# Wattuino-Nanite841_v11.net
KiCad netlist of a schematic drawn in EAGLE
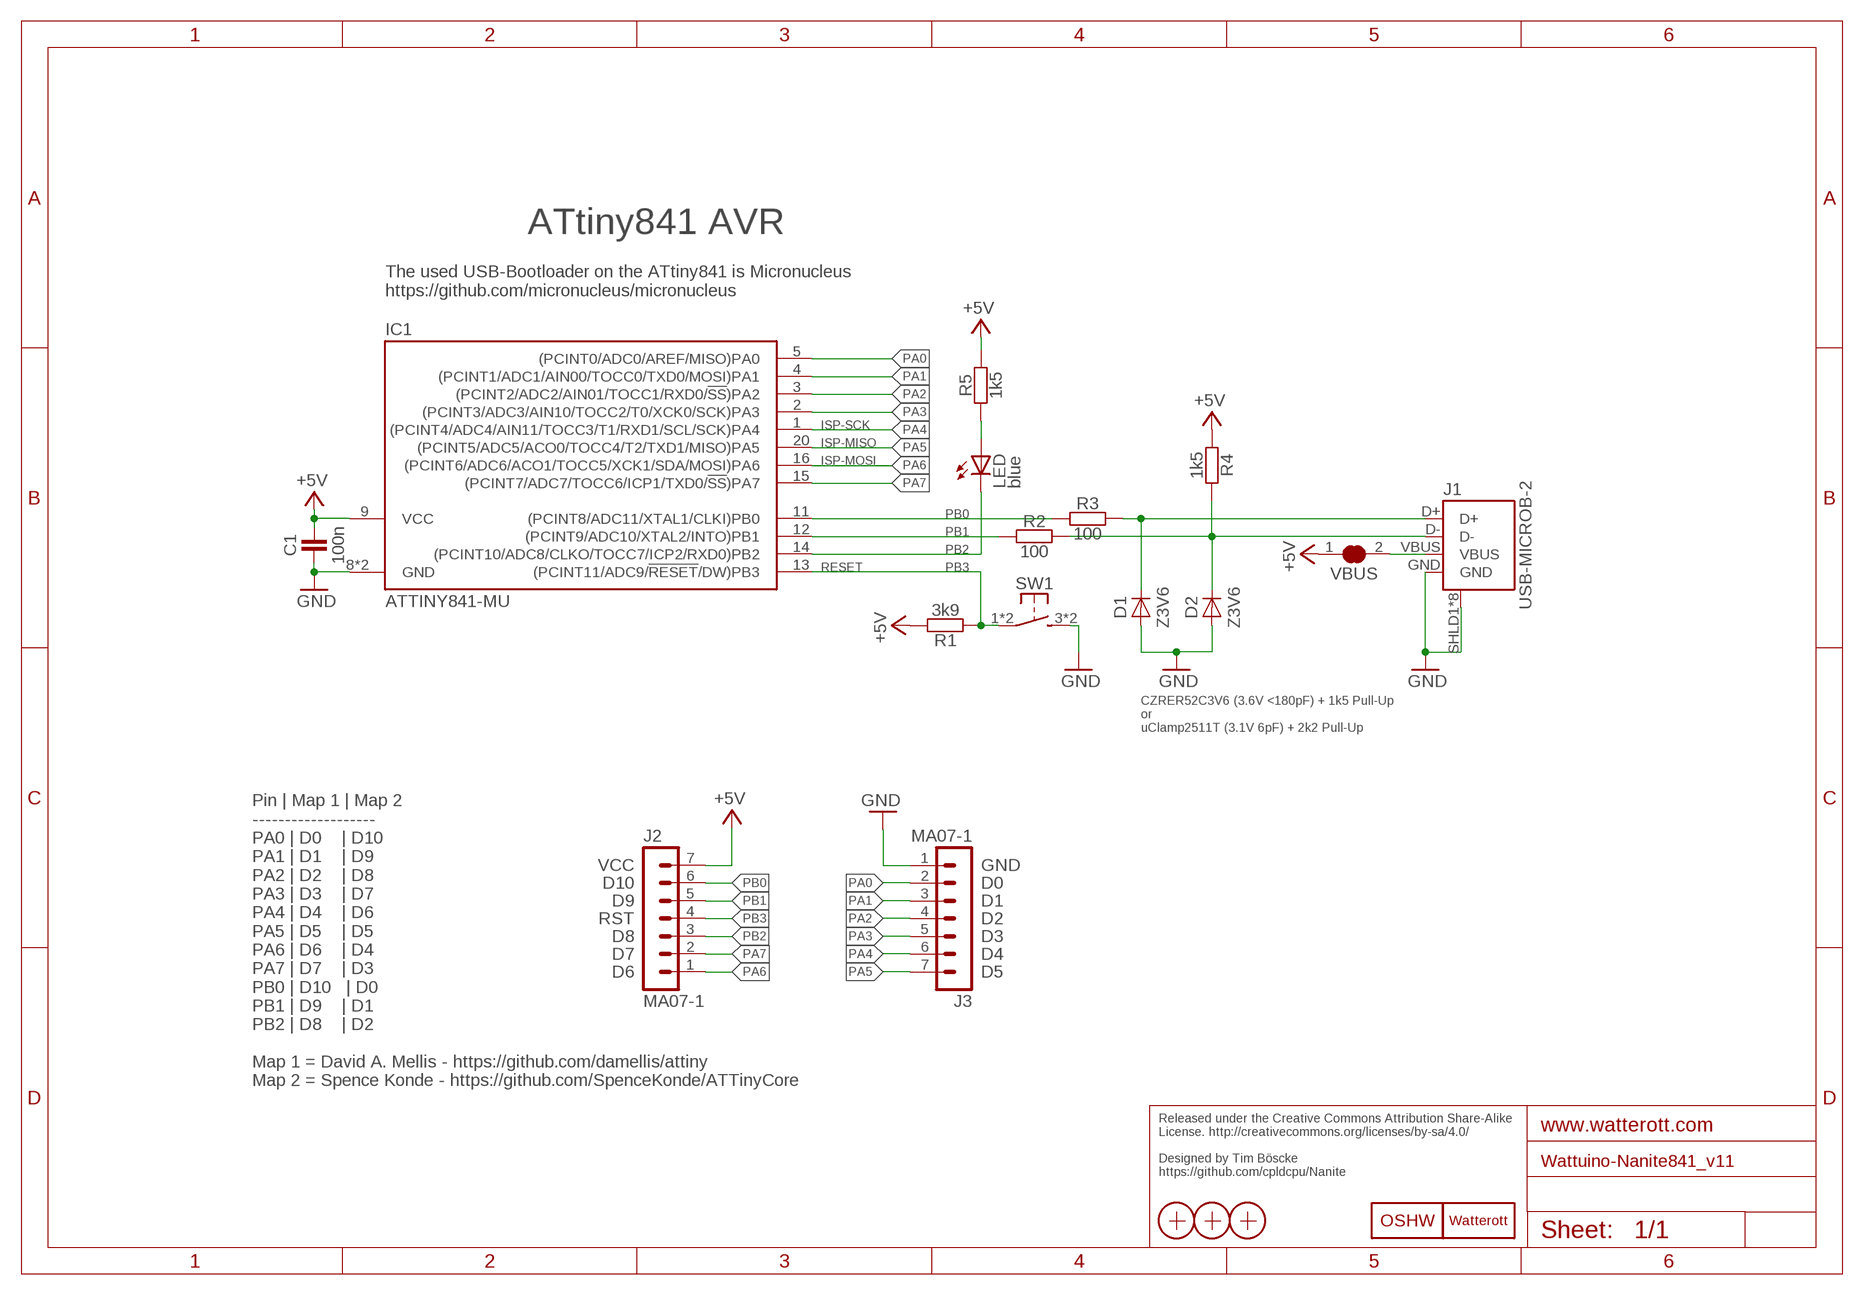
[diagram p0: schematic, sheet 1]

(export (version "E")
  (design (tool "Eeschema 10.0.6"))
  (components
    (comp (ref "C1")
      (value "100n")
      (footprint "eagle-import:C0402")
      (libsource (lib "eagle-import") (part "CAPACITOR-0402"))
    )
    (comp (ref "D1")
      (value "Z3V6")
      (footprint "eagle-import:SOD882")
      (libsource (lib "eagle-import") (part "DIODE-SOD882"))
    )
    (comp (ref "D2")
      (value "Z3V6")
      (footprint "eagle-import:SOD882")
      (libsource (lib "eagle-import") (part "DIODE-SOD882"))
    )
    (comp (ref "IC1")
      (value "ATTINY841-MU")
      (footprint "eagle-import:QFN20-PAD")
      (libsource (lib "eagle-import") (part "ATTINY841-MU"))
    )
    (comp (ref "J1")
      (value "USB-MICROB-2")
      (footprint "eagle-import:USB-MICROB-10118194")
      (libsource (lib "eagle-import") (part "USB-MICROB-2"))
    )
    (comp (ref "J2")
      (value "MA07-1")
      (footprint "eagle-import:MA07-1")
      (libsource (lib "eagle-import") (part "MA07-1"))
    )
    (comp (ref "J3")
      (value "MA07-1")
      (footprint "eagle-import:MA07-1")
      (libsource (lib "eagle-import") (part "MA07-1"))
    )
    (comp (ref "LED")
      (value "blue")
      (footprint "eagle-import:C0603")
      (libsource (lib "eagle-import") (part "LED-0603"))
    )
    (comp (ref "LOGO1")
      (value "LOGO-S_PLACE_S")
      (footprint "eagle-import:SPARK_TPLACE_S")
      (libsource (lib "eagle-import") (part "LOGO-S_PLACE_S"))
    )
    (comp (ref "LOGO2")
      (value "OSHW_LOGOX0070")
      (footprint "eagle-import:OSHW_6X70")
      (libsource (lib "eagle-import") (part "OSHW_LOGOX0070"))
    )
    (comp (ref "R1")
      (value "3k9")
      (footprint "eagle-import:C0402")
      (libsource (lib "eagle-import") (part "RESISTOR-0402"))
    )
    (comp (ref "R2")
      (value "100")
      (footprint "eagle-import:C0402")
      (libsource (lib "eagle-import") (part "RESISTOR-0402"))
    )
    (comp (ref "R3")
      (value "100")
      (footprint "eagle-import:C0402")
      (libsource (lib "eagle-import") (part "RESISTOR-0402"))
    )
    (comp (ref "R4")
      (value "1k5")
      (footprint "eagle-import:C0402")
      (libsource (lib "eagle-import") (part "RESISTOR-0402"))
    )
    (comp (ref "R5")
      (value "1k5")
      (footprint "eagle-import:C0402")
      (libsource (lib "eagle-import") (part "RESISTOR-0402"))
    )
    (comp (ref "SW1")
      (value "SW-TACTILE-PTS840P")
      (footprint "eagle-import:PTS840P")
      (libsource (lib "eagle-import") (part "SW-TACTILE-PTS840P"))
    )
    (comp (ref "VBUS")
      (value "JUMPER2-0603-NC")
      (footprint "eagle-import:JUMPER2-0603_NC")
      (libsource (lib "eagle-import") (part "JUMPER2-0603-NC"))
    )
    (comp (ref "X1")
      (value "PASSER-07")
      (footprint "eagle-import:PASSER_07MM")
      (libsource (lib "eagle-import") (part "PASSER-07"))
    )
    (comp (ref "X2")
      (value "PASSER-07")
      (footprint "eagle-import:PASSER_07MM")
      (libsource (lib "eagle-import") (part "PASSER-07"))
    )
    (comp (ref "X3")
      (value "PASSER-07")
      (footprint "eagle-import:PASSER_07MM")
      (libsource (lib "eagle-import") (part "PASSER-07"))
    )
  )
  (nets
    (net (code "1") (name "+5V") (class "Default")
      (node (ref "C1") (pin "2") (pinfunction "2_2") (pintype "passive"))
      (node (ref "IC1") (pin "9") (pinfunction "VCC_9") (pintype "power_in"))
      (node (ref "J2") (pin "7") (pinfunction "7_7") (pintype "passive"))
      (node (ref "R1") (pin "2") (pinfunction "2_2") (pintype "passive"))
      (node (ref "R4") (pin "1") (pinfunction "1_1") (pintype "passive"))
      (node (ref "R5") (pin "2") (pinfunction "2_2") (pintype "passive"))
      (node (ref "VBUS") (pin "1") (pinfunction "1_1") (pintype "passive"))
    )
    (net (code "2") (name "GND") (class "Default")
      (node (ref "C1") (pin "1") (pinfunction "1_1") (pintype "passive"))
      (node (ref "D1") (pin "A") (pinfunction "A_A") (pintype "passive"))
      (node (ref "D2") (pin "A") (pinfunction "A_A") (pintype "passive"))
      (node (ref "IC1") (pin "8") (pinfunction "GND_8") (pintype "power_in"))
      (node (ref "IC1") (pin "TP") (pinfunction "GND_TP") (pintype "power_in"))
      (node (ref "J1") (pin "GND") (pinfunction "GND_GND") (pintype "power_in"))
      (node (ref "J1") (pin "SHLD1") (pinfunction "SHIELD_SHLD1") (pintype "passive"))
      (node (ref "J1") (pin "SHLD2") (pinfunction "SHIELD_SHLD2") (pintype "passive"))
      (node (ref "J1") (pin "SHLD3") (pinfunction "SHIELD_SHLD3") (pintype "passive"))
      (node (ref "J1") (pin "SHLD4") (pinfunction "SHIELD_SHLD4") (pintype "passive"))
      (node (ref "J1") (pin "SHLD5") (pinfunction "SHIELD_SHLD5") (pintype "passive"))
      (node (ref "J1") (pin "SHLD6") (pinfunction "SHIELD_SHLD6") (pintype "passive"))
      (node (ref "J1") (pin "SHLD7") (pinfunction "SHIELD_SHLD7") (pintype "passive"))
      (node (ref "J1") (pin "SHLD8") (pinfunction "SHIELD_SHLD8") (pintype "passive"))
      (node (ref "J3") (pin "1") (pinfunction "1_1") (pintype "passive"))
      (node (ref "SW1") (pin "3") (pinfunction "S1_3") (pintype "passive"))
      (node (ref "SW1") (pin "4") (pinfunction "S1_4") (pintype "passive"))
    )
    (net (code "3") (name "Net-(D1-PadC)") (class "Default")
      (node (ref "D1") (pin "C") (pinfunction "C_C") (pintype "passive"))
      (node (ref "J1") (pin "D+") (pinfunction "D+_D+") (pintype "bidirectional"))
      (node (ref "R3") (pin "2") (pinfunction "2_2") (pintype "passive"))
    )
    (net (code "4") (name "Net-(D2-PadC)") (class "Default")
      (node (ref "D2") (pin "C") (pinfunction "C_C") (pintype "passive"))
      (node (ref "J1") (pin "D-") (pinfunction "D-_D-") (pintype "bidirectional"))
      (node (ref "R2") (pin "2") (pinfunction "2_2") (pintype "passive"))
      (node (ref "R4") (pin "2") (pinfunction "2_2") (pintype "passive"))
    )
    (net (code "5") (name "Net-(J1-PadVBUS)") (class "Default")
      (node (ref "J1") (pin "VBUS") (pinfunction "VBUS_VBUS") (pintype "power_in"))
      (node (ref "VBUS") (pin "2") (pinfunction "2_2") (pintype "passive"))
    )
    (net (code "6") (name "Net-(LED-PadA)") (class "Default")
      (node (ref "LED") (pin "A") (pinfunction "A_A") (pintype "passive"))
      (node (ref "R5") (pin "1") (pinfunction "1_1") (pintype "passive"))
    )
    (net (code "7") (name "PA0") (class "Default")
      (node (ref "IC1") (pin "5") (pinfunction "(PCINT0/ADC0/AREF/MISO)PA0_5") (pintype "bidirectional"))
      (node (ref "J3") (pin "2") (pinfunction "2_2") (pintype "passive"))
    )
    (net (code "8") (name "PA1") (class "Default")
      (node (ref "IC1") (pin "4") (pinfunction "(PCINT1/ADC1/AIN00/TOCC0/TXD0/MOSI)PA1_4") (pintype "bidirectional"))
      (node (ref "J3") (pin "3") (pinfunction "3_3") (pintype "passive"))
    )
    (net (code "9") (name "PA2") (class "Default")
      (node (ref "IC1") (pin "3") (pinfunction "(PCINT2/ADC2/AIN01/TOCC1/RXD0/~{SS})PA2_3") (pintype "bidirectional"))
      (node (ref "J3") (pin "4") (pinfunction "4_4") (pintype "passive"))
    )
    (net (code "10") (name "PA3") (class "Default")
      (node (ref "IC1") (pin "2") (pinfunction "(PCINT3/ADC3/AIN10/TOCC2/T0/XCK0/SCK)PA3_2") (pintype "bidirectional"))
      (node (ref "J3") (pin "5") (pinfunction "5_5") (pintype "passive"))
    )
    (net (code "11") (name "PA4") (class "Default")
      (node (ref "IC1") (pin "1") (pinfunction "(PCINT4/ADC4/AIN11/TOCC3/T1/RXD1/SCL/SCK)PA4_1") (pintype "bidirectional"))
      (node (ref "J3") (pin "6") (pinfunction "6_6") (pintype "passive"))
    )
    (net (code "12") (name "PA5") (class "Default")
      (node (ref "IC1") (pin "20") (pinfunction "(PCINT5/ADC5/ACO0/TOCC4/T2/TXD1/MISO)PA5_20") (pintype "bidirectional"))
      (node (ref "J3") (pin "7") (pinfunction "7_7") (pintype "passive"))
    )
    (net (code "13") (name "PA6") (class "Default")
      (node (ref "IC1") (pin "16") (pinfunction "(PCINT6/ADC6/ACO1/TOCC5/XCK1/SDA/MOSI)PA6_16") (pintype "bidirectional"))
      (node (ref "J2") (pin "1") (pinfunction "1_1") (pintype "passive"))
    )
    (net (code "14") (name "PA7") (class "Default")
      (node (ref "IC1") (pin "15") (pinfunction "(PCINT7/ADC7/TOCC6/ICP1/TXD0/~{SS})PA7_15") (pintype "bidirectional"))
      (node (ref "J2") (pin "2") (pinfunction "2_2") (pintype "passive"))
    )
    (net (code "15") (name "PB0") (class "Default")
      (node (ref "IC1") (pin "11") (pinfunction "(PCINT8/ADC11/XTAL1/CLKI)PB0_11") (pintype "bidirectional"))
      (node (ref "J2") (pin "6") (pinfunction "6_6") (pintype "passive"))
      (node (ref "R3") (pin "1") (pinfunction "1_1") (pintype "passive"))
    )
    (net (code "16") (name "PB1") (class "Default")
      (node (ref "IC1") (pin "12") (pinfunction "(PCINT9/ADC10/XTAL2/INTO)PB1_12") (pintype "bidirectional"))
      (node (ref "J2") (pin "5") (pinfunction "5_5") (pintype "passive"))
      (node (ref "R2") (pin "1") (pinfunction "1_1") (pintype "passive"))
    )
    (net (code "17") (name "PB2") (class "Default")
      (node (ref "IC1") (pin "14") (pinfunction "(PCINT10/ADC8/CLKO/TOCC7/ICP2/RXD0)PB2_14") (pintype "bidirectional"))
      (node (ref "J2") (pin "3") (pinfunction "3_3") (pintype "passive"))
      (node (ref "LED") (pin "C") (pinfunction "C_C") (pintype "passive"))
    )
    (net (code "18") (name "PB3") (class "Default")
      (node (ref "IC1") (pin "13") (pinfunction "(PCINT11/ADC9/~{RESET}/DW)PB3_13") (pintype "bidirectional"))
      (node (ref "J2") (pin "4") (pinfunction "4_4") (pintype "passive"))
      (node (ref "R1") (pin "1") (pinfunction "1_1") (pintype "passive"))
      (node (ref "SW1") (pin "1") (pinfunction "P1_1") (pintype "passive"))
      (node (ref "SW1") (pin "2") (pinfunction "P1_2") (pintype "passive"))
    )
  )
)
